# synchronous.net
KiCad netlist of a schematic drawn in Altium Designer
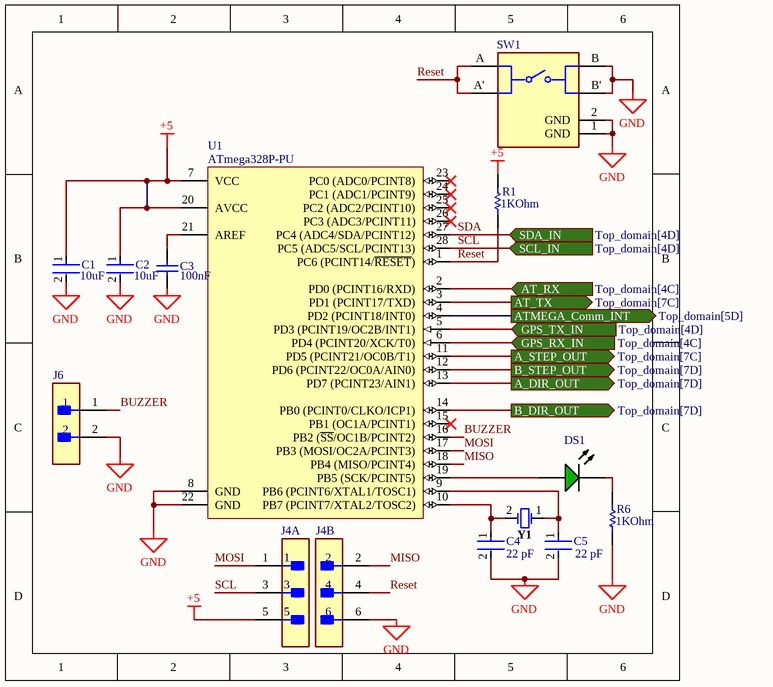
[diagram p0: synchronous.SchDoc]

(export (version "E")
  (design (tool "Eeschema 10.0.6"))
  (components
    (comp (ref "C1")
      (value "1206YD106KAT2A")
      (footprint "FP-1206-L_3_2_0_2-W_1_6_0-IPC_B")
      (description "General Purpose Ceramic Capacitor, 1206, 10uF, 10%, X5R, 15%, 16V")
      (fields
        (field (name "TOLERANCE") "10%")
        (field (name "CAPACITANCE") "10uF")
        (field (name "VOLTAGE") "16V")
      )
      (libsource (lib "Altium Content Vault") (part "02cd4be3c70576c341d710602a673aa"))
    )
    (comp (ref "C2")
      (value "1206YD106KAT2A")
      (footprint "FP-1206-L_3_2_0_2-W_1_6_0-IPC_B")
      (description "General Purpose Ceramic Capacitor, 1206, 10uF, 10%, X5R, 15%, 16V")
      (fields
        (field (name "TOLERANCE") "10%")
        (field (name "CAPACITANCE") "10uF")
        (field (name "VOLTAGE") "16V")
      )
      (libsource (lib "Altium Content Vault") (part "02cd4be3c70576c341d710602a673aa"))
    )
    (comp (ref "C3")
      (value "100nF")
      (footprint "CAPC2013X140X50LL20T25")
      (fields
        (field (name "MANUFACTURER") "AVX Interconnect / Elco")
        (field (name "PART NUMBER") "08055F104KAT2A")
      )
      (libsource (lib "Altium Content Vault") (part "CAP"))
    )
    (comp (ref "C4")
      (value "C0805C220K3GACTU")
      (footprint "FP-C0805C-DN-MFG")
      (description "CAP CER 22PF 25V 10% NP0 0805")
      (fields
        (field (name "TOLERANCE") "0.1")
        (field (name "OCTOPART") "https://octopart.com/c0805c220k3gactu-kemet-12580612")
        (field (name "CAPACITANCE") "22 pF")
      )
      (libsource (lib "Altium Content Vault") (part "b4654b650e69147ec39a6b967a45e02"))
    )
    (comp (ref "C5")
      (value "C0805C220K3GACTU")
      (footprint "FP-C0805C-DN-MFG")
      (description "CAP CER 22PF 25V 10% NP0 0805")
      (fields
        (field (name "TOLERANCE") "0.1")
        (field (name "OCTOPART") "https://octopart.com/c0805c220k3gactu-kemet-12580612")
        (field (name "CAPACITANCE") "22 pF")
      )
      (libsource (lib "Altium Content Vault") (part "b4654b650e69147ec39a6b967a45e02"))
    )
    (comp (ref "DS1")
      (value "HSMG-C170")
      (footprint "AVAG-HSMX-C170_V")
      (description "Chip LED, Green, 2.2 V, -40 to 85 degC, 2-Pin SMD, Pb-Free, Tape and Reel")
      (fields (field (name "MANUFACTURER") "Avago"))
      (libsource (lib "Altium Content Vault") (part "LED_GREEN_A1K2-2"))
    )
    (comp (ref "J4")
      (value "M20-9980346")
      (footprint "FP-M20-9980346-MFG")
      (description "CONN HEADER VERT 6POS 2.54MM")
      (fields
        (field (name "MANUFACTURER") "Harwin")
        (field (name "OCTOPART") "https://octopart.com/m20-9980346-harwin-5436545")
      )
      (libsource (lib "Altium Content Vault") (part "2654a11fb13586ecb194516b1c997bc"))
    )
    (comp (ref "J6")
      (value "B2B-XH-A(LF)(SN)")
      (footprint "FP-B2B-XH-A_LF_SN-MFG")
      (description "CONN HEADER VERT 2POS 2.5MM")
      (libsource (lib "Altium Content Vault") (part "3bc925449376181038e59eaffc5286c"))
    )
    (comp (ref "R1")
      (value "RC0805FR-071KL")
      (footprint "RESC2013X60X35ML10T20")
      (description "Chip Resistor, 1 KOhm, +/- 1%, 125 mW, -55 to 155 degC, 0805 (2012 Metric), RoHS, Tape and Reel")
      (fields
        (field (name "RESISTANCE") "1KOhm")
        (field (name "TOLERANCE") "1%")
        (field (name "MANUFACTURER") "Yageo")
      )
      (libsource (lib "Altium Content Vault") (part "RES-2"))
    )
    (comp (ref "R6")
      (value "RC0805FR-071KL")
      (footprint "RESC2013X60X35ML10T20")
      (description "Chip Resistor, 1 KOhm, +/- 1%, 125 mW, -55 to 155 degC, 0805 (2012 Metric), RoHS, Tape and Reel")
      (fields
        (field (name "RESISTANCE") "1KOhm")
        (field (name "TOLERANCE") "1%")
        (field (name "MANUFACTURER") "Yageo")
      )
      (libsource (lib "Altium Content Vault") (part "RES-2"))
    )
    (comp (ref "SW1")
      (value "EVQ-PLMA15")
      (footprint "FP-EVQ-PLMA15-MFG")
      (description "SWITCH TACTILE SPST-NO 0.02A 15V")
      (fields
        (field (name "OCTOPART") "https://octopart.com/evq-plma15-panasonic-39850235")
        (field (name "MANUFACTURER") "Panasonic Electronic Components")
      )
      (libsource (lib "Altium Content Vault") (part "fc7b47d2e4813f0909612a6c4f63938"))
    )
    (comp (ref "U1")
      (value "ATmega328P-PU")
      (footprint "28P3")
      (libsource (lib "Altium Content Vault") (part "MC-8B-ATM48-IL28"))
    )
    (comp (ref "Y1")
      (value "FOXSLF/160-20")
      (footprint "FOX-FOXSLF160-20")
      (description "Resistance Weld Thru-Hole Crystal, 16 MHz, -20 to 70 degC, 2-Pin THD, RoHS, Bulk")
      (fields (field (name "TOLERANCE") "1%"))
      (libsource (lib "Altium Content Vault") (part "XTAL-1-2-2"))
    )
  )
  (nets
    (net (code "1") (name "+5") (class "Default")
      (node (ref "C1") (pin "1") (pinfunction "1_1") (pintype "passive"))
      (node (ref "C2") (pin "1") (pinfunction "1_1") (pintype "passive"))
      (node (ref "J4") (pin "5") (pinfunction "5_5") (pintype "passive"))
      (node (ref "R1") (pin "2") (pinfunction "2_2") (pintype "passive"))
      (node (ref "U1") (pin "20") (pinfunction "AVCC_20") (pintype "power_in"))
      (node (ref "U1") (pin "7") (pinfunction "VCC_7") (pintype "power_in"))
    )
    (net (code "2") (name "/ATMEGA_Comm_INT") (class "Default")
      (node (ref "U1") (pin "4") (pinfunction "PD2_(PCINT18/INT0)_4") (pintype "bidirectional"))
    )
    (net (code "3") (name "/AT_RX") (class "Default")
      (node (ref "U1") (pin "2") (pinfunction "PD0_(PCINT16/RXD)_2") (pintype "bidirectional"))
    )
    (net (code "4") (name "/AT_TX") (class "Default")
      (node (ref "U1") (pin "3") (pinfunction "PD1_(PCINT17/TXD)_3") (pintype "bidirectional"))
    )
    (net (code "5") (name "/A_DIR_OUT") (class "Default")
      (node (ref "U1") (pin "13") (pinfunction "PD7_(PCINT23/AIN1)_13") (pintype "bidirectional"))
    )
    (net (code "6") (name "/A_STEP_OUT") (class "Default")
      (node (ref "U1") (pin "11") (pinfunction "PD5_(PCINT21/OC0B/T1)_11") (pintype "bidirectional"))
    )
    (net (code "7") (name "/BUZZER") (class "Default")
      (node (ref "J6") (pin "1") (pinfunction "1_1") (pintype "passive"))
      (node (ref "U1") (pin "16") (pinfunction "PB2_(~{SS}/OC1B/PCINT2)_16") (pintype "bidirectional"))
    )
    (net (code "8") (name "/B_DIR_OUT") (class "Default")
      (node (ref "U1") (pin "14") (pinfunction "PB0_(PCINT0/CLKO/ICP1)_14") (pintype "bidirectional"))
    )
    (net (code "9") (name "/B_STEP_OUT") (class "Default")
      (node (ref "U1") (pin "12") (pinfunction "PD6_(PCINT22/OC0A/AIN0)_12") (pintype "bidirectional"))
    )
    (net (code "10") (name "/GPS_RX_IN") (class "Default")
      (node (ref "U1") (pin "6") (pinfunction "PD4_(PCINT20/XCK/T0)_6") (pintype "input"))
    )
    (net (code "11") (name "/GPS_TX_IN") (class "Default")
      (node (ref "U1") (pin "5") (pinfunction "PD3_(PCINT19/OC2B/INT1)_5") (pintype "input"))
    )
    (net (code "12") (name "/MISO") (class "Default")
      (node (ref "J4") (pin "2") (pinfunction "2_2") (pintype "passive"))
      (node (ref "U1") (pin "18") (pinfunction "PB4_(MISO/PCINT4)_18") (pintype "bidirectional"))
    )
    (net (code "13") (name "/MOSI") (class "Default")
      (node (ref "J4") (pin "1") (pinfunction "1_1") (pintype "passive"))
      (node (ref "U1") (pin "17") (pinfunction "PB3_(MOSI/OC2A/PCINT3)_17") (pintype "bidirectional"))
    )
    (net (code "14") (name "/Reset") (class "Default")
      (node (ref "J4") (pin "4") (pinfunction "4_4") (pintype "passive"))
      (node (ref "R1") (pin "1") (pinfunction "1_1") (pintype "passive"))
      (node (ref "SW1") (pin "A") (pinfunction "A_A") (pintype "passive"))
      (node (ref "SW1") (pin "A'") (pinfunction "A'_A'") (pintype "passive"))
      (node (ref "U1") (pin "1") (pinfunction "PC6_(PCINT14/~{RESET})_1") (pintype "bidirectional"))
    )
    (net (code "15") (name "/SCL") (class "Default")
      (node (ref "J4") (pin "3") (pinfunction "3_3") (pintype "passive"))
      (node (ref "U1") (pin "28") (pinfunction "PC5_(ADC5/SCL/PCINT13)_28") (pintype "bidirectional"))
    )
    (net (code "17") (name "/SDA_IN") (class "Default")
      (node (ref "U1") (pin "27") (pinfunction "PC4_(ADC4/SDA/PCINT12)_27") (pintype "bidirectional"))
    )
    (net (code "18") (name "GND") (class "Default")
      (node (ref "C1") (pin "2") (pinfunction "2_2") (pintype "passive"))
      (node (ref "C2") (pin "2") (pinfunction "2_2") (pintype "passive"))
      (node (ref "C3") (pin "1") (pinfunction "1_1") (pintype "passive"))
      (node (ref "C4") (pin "2") (pinfunction "2_2") (pintype "passive"))
      (node (ref "C5") (pin "2") (pinfunction "2_2") (pintype "passive"))
      (node (ref "J4") (pin "6") (pinfunction "6_6") (pintype "passive"))
      (node (ref "J6") (pin "2") (pinfunction "2_2") (pintype "passive"))
      (node (ref "R6") (pin "1") (pinfunction "1_1") (pintype "passive"))
      (node (ref "SW1") (pin "1") (pinfunction "GND_1") (pintype "power_in"))
      (node (ref "SW1") (pin "2") (pinfunction "GND_2") (pintype "power_in"))
      (node (ref "SW1") (pin "B") (pinfunction "B_B") (pintype "passive"))
      (node (ref "SW1") (pin "B'") (pinfunction "B'_B'") (pintype "passive"))
      (node (ref "U1") (pin "22") (pinfunction "GND_22") (pintype "power_in"))
      (node (ref "U1") (pin "8") (pinfunction "GND_8") (pintype "power_in"))
    )
    (net (code "19") (name "Net-(DS1-A)") (class "Default")
      (node (ref "DS1") (pin "1") (pinfunction "A_1") (pintype "passive"))
      (node (ref "U1") (pin "19") (pinfunction "PB5_(SCK/PCINT5)_19") (pintype "bidirectional"))
    )
    (net (code "20") (name "Net-(DS1-K)") (class "Default")
      (node (ref "DS1") (pin "2") (pinfunction "K_2") (pintype "passive"))
      (node (ref "R6") (pin "2") (pinfunction "2_2") (pintype "passive"))
    )
    (net (code "21") (name "Net-(U1-AREF)") (class "Default")
      (node (ref "C3") (pin "2") (pinfunction "2_2") (pintype "passive"))
      (node (ref "U1") (pin "21") (pinfunction "AREF_21") (pintype "power_in"))
    )
    (net (code "22") (name "Net-(U1-PB6_(PCINT6{slash}XTAL1{slash}TOSC1))") (class "Default")
      (node (ref "C5") (pin "1") (pinfunction "1_1") (pintype "passive"))
      (node (ref "U1") (pin "9") (pinfunction "PB6_(PCINT6/XTAL1/TOSC1)_9") (pintype "bidirectional"))
      (node (ref "Y1") (pin "1") (pinfunction "1_1") (pintype "passive"))
    )
    (net (code "23") (name "Net-(U1-PB7_(PCINT7{slash}XTAL2{slash}TOSC2))") (class "Default")
      (node (ref "C4") (pin "1") (pinfunction "1_1") (pintype "passive"))
      (node (ref "U1") (pin "10") (pinfunction "PB7_(PCINT7/XTAL2/TOSC2)_10") (pintype "bidirectional"))
      (node (ref "Y1") (pin "2") (pinfunction "2_2") (pintype "passive"))
    )
    (net (code "24") (name "unconnected-(U1-PB1_(OC1A{slash}PCINT1)-Pad15)") (class "Default")
      (node (ref "U1") (pin "15") (pinfunction "PB1_(OC1A/PCINT1)_15") (pintype "bidirectional+no_connect"))
    )
    (net (code "25") (name "unconnected-(U1-PC0_(ADC0{slash}PCINT8)-Pad23)") (class "Default")
      (node (ref "U1") (pin "23") (pinfunction "PC0_(ADC0/PCINT8)_23") (pintype "bidirectional+no_connect"))
    )
    (net (code "26") (name "unconnected-(U1-PC1_(ADC1{slash}PCINT9)-Pad24)") (class "Default")
      (node (ref "U1") (pin "24") (pinfunction "PC1_(ADC1/PCINT9)_24") (pintype "bidirectional+no_connect"))
    )
    (net (code "27") (name "unconnected-(U1-PC2_(ADC2{slash}PCINT10)-Pad25)") (class "Default")
      (node (ref "U1") (pin "25") (pinfunction "PC2_(ADC2/PCINT10)_25") (pintype "bidirectional+no_connect"))
    )
    (net (code "28") (name "unconnected-(U1-PC3_(ADC3{slash}PCINT11)-Pad26)") (class "Default")
      (node (ref "U1") (pin "26") (pinfunction "PC3_(ADC3/PCINT11)_26") (pintype "bidirectional+no_connect"))
    )
  )
)
